# batboard.net
KiCad netlist of a schematic drawn in EAGLE
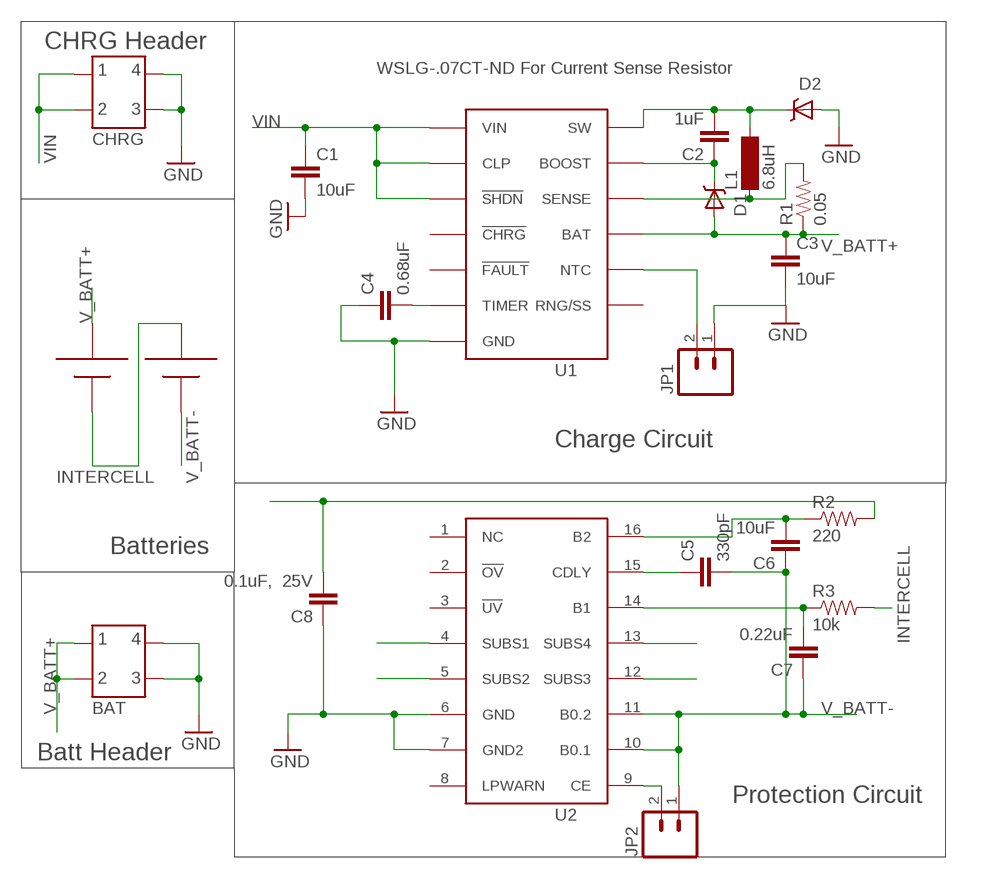
[diagram p0: schematic, sheet 1]

(export (version "E")
  (design (tool "Eeschema 10.0.6"))
  (components
    (comp (ref "BAT")
      (value "C-GRID-71308")
      (footprint "eagle-import:4HEAD_MOLEX_C71308")
      (libsource (lib "eagle-import") (part "C-GRID-71308"))
    )
    (comp (ref "C1")
      (value "10uF")
      (footprint "eagle-import:0805")
      (libsource (lib "eagle-import") (part "CAP0805"))
    )
    (comp (ref "C2")
      (value "1uF")
      (footprint "eagle-import:0805")
      (libsource (lib "eagle-import") (part "CAP0805"))
    )
    (comp (ref "C3")
      (value "10uF")
      (footprint "eagle-import:0805")
      (libsource (lib "eagle-import") (part "CAP0805"))
    )
    (comp (ref "C4")
      (value "0.68uF")
      (footprint "eagle-import:0805")
      (libsource (lib "eagle-import") (part "CAP0805"))
    )
    (comp (ref "C5")
      (value "330pF")
      (footprint "eagle-import:0805")
      (libsource (lib "eagle-import") (part "CAP0805"))
    )
    (comp (ref "C6")
      (value "10uF")
      (footprint "eagle-import:0805")
      (libsource (lib "eagle-import") (part "CAP0805"))
    )
    (comp (ref "C7")
      (value "0.22uF")
      (footprint "eagle-import:0805")
      (libsource (lib "eagle-import") (part "CAP0805"))
    )
    (comp (ref "C8")
      (value "0.1uF, 25V")
      (footprint "eagle-import:0805")
      (libsource (lib "eagle-import") (part "CAP0805"))
    )
    (comp (ref "CHRG")
      (value "C-GRID-71308")
      (footprint "eagle-import:4HEAD_MOLEX_C71308")
      (libsource (lib "eagle-import") (part "C-GRID-71308"))
    )
    (comp (ref "D1")
      (value "DIODE-SCHOTTKY_")
      (footprint "eagle-import:SMA-DIODE")
      (libsource (lib "eagle-import") (part "DIODE-SCHOTTKY_"))
    )
    (comp (ref "D2")
      (value "DIODE-SCHOTTKY_")
      (footprint "eagle-import:SMA-DIODE")
      (libsource (lib "eagle-import") (part "DIODE-SCHOTTKY_"))
    )
    (comp (ref "JP1")
      (value "M02PTH")
      (footprint "eagle-import:1X02")
      (libsource (lib "eagle-import") (part "M02PTH"))
    )
    (comp (ref "JP2")
      (value "M02PTH")
      (footprint "eagle-import:1X02")
      (libsource (lib "eagle-import") (part "M02PTH"))
    )
    (comp (ref "L1")
      (value "6.8uH")
      (footprint "eagle-import:SM-1206")
      (libsource (lib "eagle-import") (part "SM-1206"))
    )
    (comp (ref "R1")
      (value "0.05")
      (footprint "eagle-import:R2512")
      (libsource (lib "eagle-import") (part "RESISTOR2512"))
    )
    (comp (ref "R2")
      (value "220")
      (footprint "eagle-import:0603-RES")
      (libsource (lib "eagle-import") (part "RESISTOR0603-RES"))
    )
    (comp (ref "R3")
      (value "10k")
      (footprint "eagle-import:0603-RES")
      (libsource (lib "eagle-import") (part "RESISTOR0603-RES"))
    )
    (comp (ref "U$1")
      (value "BK-18650-PC4")
      (footprint "eagle-import:18650-PC4")
      (libsource (lib "eagle-import") (part "BK-18650-PC4"))
    )
    (comp (ref "U1")
      (value "LT3650")
      (footprint "eagle-import:12-MSOP")
      (libsource (lib "eagle-import") (part "LT3650"))
    )
    (comp (ref "U2")
      (value "UCC3911")
      (footprint "eagle-import:SOIC-16")
      (libsource (lib "eagle-import") (part "UCC3911"))
    )
  )
  (nets
    (net (code "1") (name "/HSINK") (class "Default")
      (node (ref "U2") (pin "12") (pinfunction "SUBS3_12") (pintype "bidirectional"))
      (node (ref "U2") (pin "13") (pinfunction "SUBS4_13") (pintype "bidirectional"))
      (node (ref "U2") (pin "4") (pinfunction "SUBS1_4") (pintype "bidirectional"))
      (node (ref "U2") (pin "5") (pinfunction "SUBS2_5") (pintype "bidirectional"))
    )
    (net (code "2") (name "/INTERCELL") (class "Default")
      (node (ref "R3") (pin "2") (pinfunction "2_2") (pintype "passive"))
      (node (ref "U$1") (pin "+2") (pinfunction "+2_+2") (pintype "bidirectional"))
      (node (ref "U$1") (pin "-1") (pinfunction "-1_-1") (pintype "bidirectional"))
    )
    (net (code "3") (name "/VIN") (class "Default")
      (node (ref "C1") (pin "1") (pinfunction "1_1") (pintype "passive"))
      (node (ref "CHRG") (pin "1") (pinfunction "1_1") (pintype "bidirectional"))
      (node (ref "CHRG") (pin "2") (pinfunction "2_2") (pintype "bidirectional"))
      (node (ref "U1") (pin "1") (pinfunction "VIN_1") (pintype "bidirectional"))
      (node (ref "U1") (pin "2") (pinfunction "CLP_2") (pintype "bidirectional"))
      (node (ref "U1") (pin "3") (pinfunction "~{SHDN}_3") (pintype "bidirectional"))
    )
    (net (code "4") (name "/V_BATT+") (class "Default")
      (node (ref "BAT") (pin "1") (pinfunction "1_1") (pintype "bidirectional"))
      (node (ref "BAT") (pin "2") (pinfunction "2_2") (pintype "bidirectional"))
      (node (ref "C3") (pin "1") (pinfunction "1_1") (pintype "passive"))
      (node (ref "C8") (pin "2") (pinfunction "2_2") (pintype "passive"))
      (node (ref "D1") (pin "A") (pinfunction "A_A") (pintype "passive"))
      (node (ref "R1") (pin "1") (pinfunction "1_1") (pintype "passive"))
      (node (ref "R2") (pin "2") (pinfunction "2_2") (pintype "passive"))
      (node (ref "U$1") (pin "+1") (pinfunction "+1_+1") (pintype "bidirectional"))
      (node (ref "U1") (pin "9") (pinfunction "BAT_9") (pintype "bidirectional"))
    )
    (net (code "5") (name "/V_BATT-") (class "Default")
      (node (ref "C5") (pin "2") (pinfunction "2_2") (pintype "passive"))
      (node (ref "C6") (pin "1") (pinfunction "1_1") (pintype "passive"))
      (node (ref "C7") (pin "1") (pinfunction "1_1") (pintype "passive"))
      (node (ref "JP2") (pin "1") (pinfunction "1_1") (pintype "passive"))
      (node (ref "U$1") (pin "-2") (pinfunction "-2_-2") (pintype "bidirectional"))
      (node (ref "U2") (pin "10") (pinfunction "B0.1_10") (pintype "bidirectional"))
      (node (ref "U2") (pin "11") (pinfunction "B0.2_11") (pintype "bidirectional"))
    )
    (net (code "6") (name "GND") (class "Default")
      (node (ref "BAT") (pin "3") (pinfunction "3_3") (pintype "bidirectional"))
      (node (ref "BAT") (pin "4") (pinfunction "4_4") (pintype "bidirectional"))
      (node (ref "C1") (pin "2") (pinfunction "2_2") (pintype "passive"))
      (node (ref "C3") (pin "2") (pinfunction "2_2") (pintype "passive"))
      (node (ref "C4") (pin "1") (pinfunction "1_1") (pintype "passive"))
      (node (ref "C8") (pin "1") (pinfunction "1_1") (pintype "passive"))
      (node (ref "CHRG") (pin "3") (pinfunction "3_3") (pintype "bidirectional"))
      (node (ref "CHRG") (pin "4") (pinfunction "4_4") (pintype "bidirectional"))
      (node (ref "D2") (pin "A") (pinfunction "A_A") (pintype "passive"))
      (node (ref "JP1") (pin "1") (pinfunction "1_1") (pintype "passive"))
      (node (ref "U1") (pin "GND") (pinfunction "GND_GND") (pintype "bidirectional"))
      (node (ref "U2") (pin "6") (pinfunction "GND_6") (pintype "bidirectional"))
      (node (ref "U2") (pin "7") (pinfunction "GND2_7") (pintype "bidirectional"))
    )
    (net (code "7") (name "Net-(U1-BOOST)") (class "Default")
      (node (ref "C2") (pin "1") (pinfunction "1_1") (pintype "passive"))
      (node (ref "D1") (pin "C") (pinfunction "C_C") (pintype "passive"))
      (node (ref "U1") (pin "11") (pinfunction "BOOST_11") (pintype "bidirectional"))
    )
    (net (code "8") (name "Net-(U1-NTC)") (class "Default")
      (node (ref "JP1") (pin "2") (pinfunction "2_2") (pintype "passive"))
      (node (ref "U1") (pin "8") (pinfunction "NTC_8") (pintype "bidirectional"))
    )
    (net (code "9") (name "Net-(U1-SENSE)") (class "Default")
      (node (ref "L1") (pin "1") (pinfunction "1_1") (pintype "passive"))
      (node (ref "R1") (pin "2") (pinfunction "2_2") (pintype "passive"))
      (node (ref "U1") (pin "10") (pinfunction "SENSE_10") (pintype "bidirectional"))
    )
    (net (code "10") (name "Net-(U1-SW)") (class "Default")
      (node (ref "C2") (pin "2") (pinfunction "2_2") (pintype "passive"))
      (node (ref "D2") (pin "C") (pinfunction "C_C") (pintype "passive"))
      (node (ref "L1") (pin "2") (pinfunction "2_2") (pintype "passive"))
      (node (ref "U1") (pin "12") (pinfunction "SW_12") (pintype "bidirectional"))
    )
    (net (code "11") (name "Net-(U1-TIMER)") (class "Default")
      (node (ref "C4") (pin "2") (pinfunction "2_2") (pintype "passive"))
      (node (ref "U1") (pin "6") (pinfunction "TIMER_6") (pintype "bidirectional"))
    )
    (net (code "12") (name "Net-(U2-B1)") (class "Default")
      (node (ref "C7") (pin "2") (pinfunction "2_2") (pintype "passive"))
      (node (ref "R3") (pin "1") (pinfunction "1_1") (pintype "passive"))
      (node (ref "U2") (pin "14") (pinfunction "B1_14") (pintype "bidirectional"))
    )
    (net (code "13") (name "Net-(U2-B2)") (class "Default")
      (node (ref "C6") (pin "2") (pinfunction "2_2") (pintype "passive"))
      (node (ref "R2") (pin "1") (pinfunction "1_1") (pintype "passive"))
      (node (ref "U2") (pin "16") (pinfunction "B2_16") (pintype "bidirectional"))
    )
    (net (code "14") (name "Net-(U2-CDLY)") (class "Default")
      (node (ref "C5") (pin "1") (pinfunction "1_1") (pintype "passive"))
      (node (ref "U2") (pin "15") (pinfunction "CDLY_15") (pintype "bidirectional"))
    )
    (net (code "15") (name "Net-(U2-CE)") (class "Default")
      (node (ref "JP2") (pin "2") (pinfunction "2_2") (pintype "passive"))
      (node (ref "U2") (pin "9") (pinfunction "CE_9") (pintype "bidirectional"))
    )
    (net (code "16") (name "unconnected-(U1-RNG{slash}SS-Pad7)") (class "Default")
      (node (ref "U1") (pin "7") (pinfunction "RNG/SS_7") (pintype "bidirectional"))
    )
    (net (code "17") (name "unconnected-(U1-~{CHRG}-Pad4)") (class "Default")
      (node (ref "U1") (pin "4") (pinfunction "~{CHRG}_4") (pintype "bidirectional"))
    )
    (net (code "18") (name "unconnected-(U1-~{FAULT}-Pad5)") (class "Default")
      (node (ref "U1") (pin "5") (pinfunction "~{FAULT}_5") (pintype "bidirectional"))
    )
    (net (code "19") (name "unconnected-(U2-LPWARN-Pad8)") (class "Default")
      (node (ref "U2") (pin "8") (pinfunction "LPWARN_8") (pintype "bidirectional"))
    )
    (net (code "20") (name "unconnected-(U2-NC-Pad1)") (class "Default")
      (node (ref "U2") (pin "1") (pinfunction "NC_1") (pintype "bidirectional"))
    )
    (net (code "21") (name "unconnected-(U2-~{OV}-Pad2)") (class "Default")
      (node (ref "U2") (pin "2") (pinfunction "~{OV}_2") (pintype "bidirectional"))
    )
    (net (code "22") (name "unconnected-(U2-~{UV}-Pad3)") (class "Default")
      (node (ref "U2") (pin "3") (pinfunction "~{UV}_3") (pintype "bidirectional"))
    )
  )
)
